# CW340_FPGA_CFG.net
KiCad netlist of a schematic drawn in Altium Designer
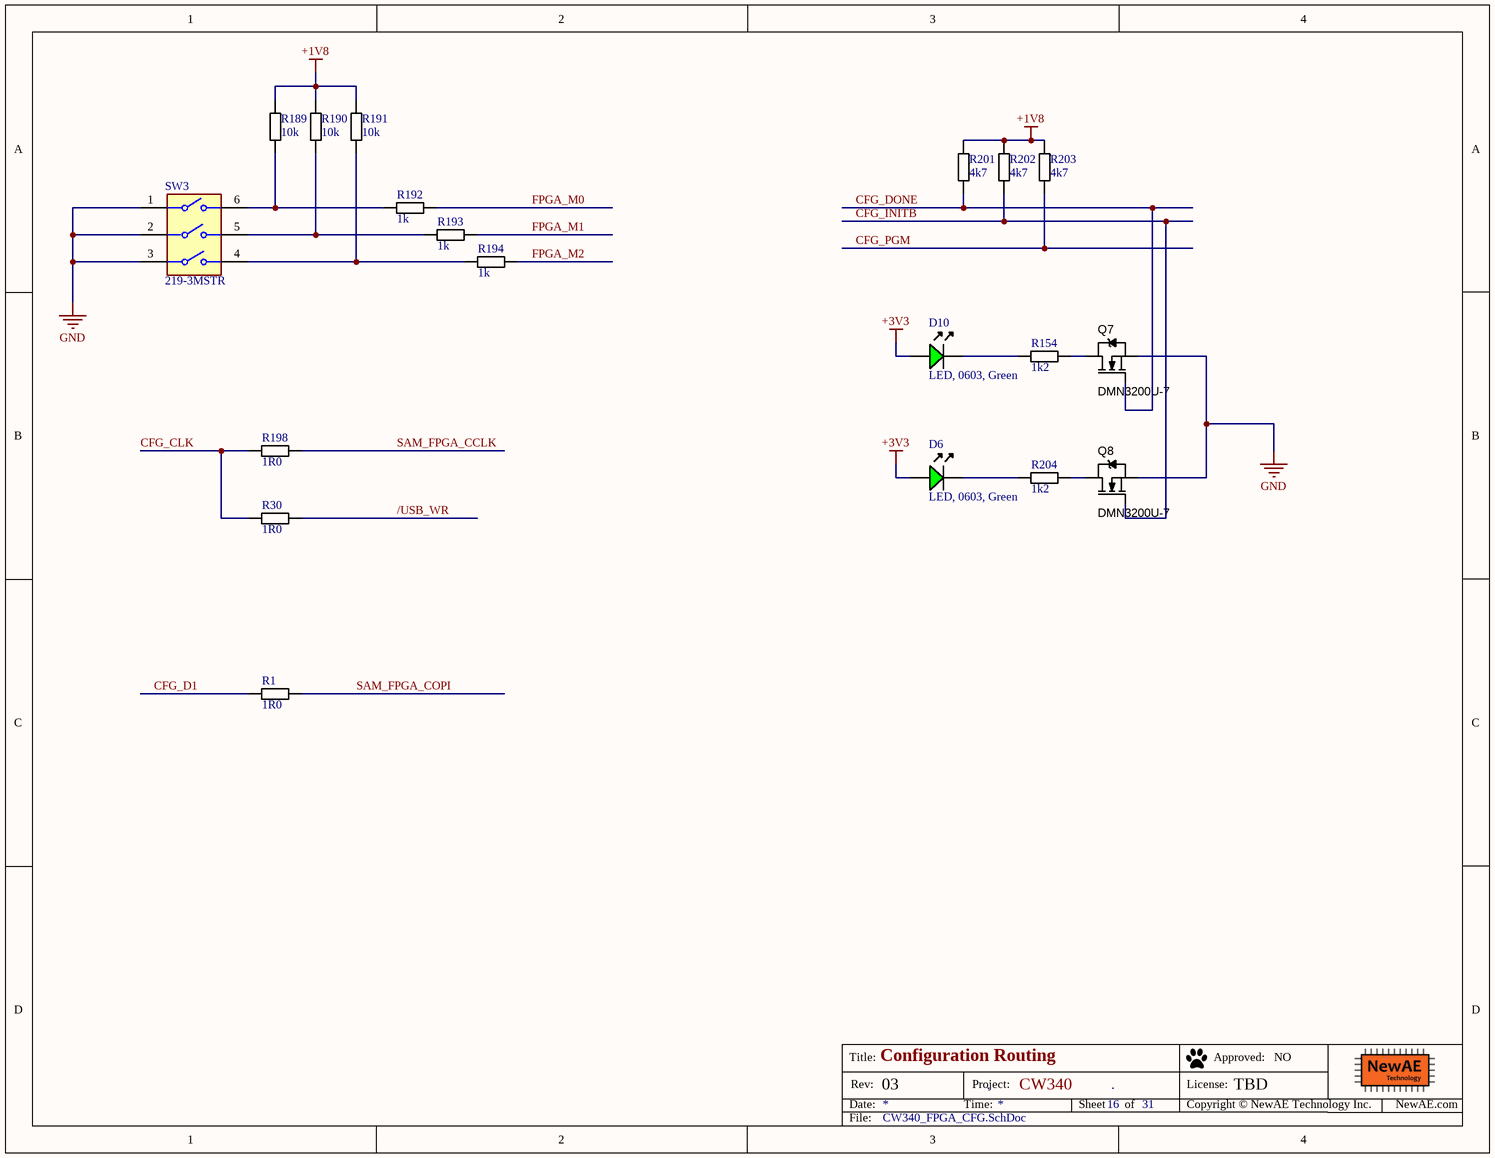
[diagram p0: CW340_FPGA_CFG.SchDoc]

(export (version "E")
  (design (tool "Eeschema 10.0.6"))
  (components
    (comp (ref "D6")
      (value "LED, 0603, Green")
      (footprint "LED-0603-GREEN")
      (description "Chip LED, Green")
      (fields (field (name "PART NUMBER") "LEDCHIP_0603_GREEN"))
      (libsource (lib "NewAE_AltiumLib") (part "LED_GREEN"))
    )
    (comp (ref "D10")
      (value "LED, 0603, Green")
      (footprint "LED-0603-GREEN")
      (description "Chip LED, Green")
      (fields (field (name "PART NUMBER") "LEDCHIP_0603_GREEN"))
      (libsource (lib "NewAE_AltiumLib") (part "LED_GREEN"))
    )
    (comp (ref "Q7")
      (value "DMN3200U-7")
      (footprint "SOT95P245X110-3M")
      (description "MOSFET N-CH 30V 2.2A SOT23-3")
      (libsource (lib "NewAE_AltiumLib") (part "MOSFET_N_GSD"))
    )
    (comp (ref "Q8")
      (value "DMN3200U-7")
      (footprint "SOT95P245X110-3M")
      (description "MOSFET N-CH 30V 2.2A SOT23-3")
      (libsource (lib "NewAE_AltiumLib") (part "MOSFET_N_GSD"))
    )
    (comp (ref "R1")
      (value "1R0")
      (footprint "RESC1608X55N")
      (description "1R0 res, 0603, 1%, 1/10W")
      (fields (field (name "PART NUMBER") "RCHIP-1R0-0603") (field (name "TOLERANCE") "1%"))
      (libsource (lib "") (part "RES-EU_1"))
    )
    (comp (ref "R30")
      (value "1R0")
      (footprint "RESC1608X55N")
      (description "1R0 res, 0603, 1%, 1/10W")
      (fields (field (name "PART NUMBER") "RCHIP-1R0-0603") (field (name "TOLERANCE") "1%"))
      (libsource (lib "") (part "RES-EU_1"))
    )
    (comp (ref "R154")
      (value "1k2")
      (footprint "RESC1005X40N")
      (description "1k2 res, 0402, 1%, 1/16W")
      (fields (field (name "PART NUMBER") "RCHIP-1K2-0402") (field (name "TOLERANCE") "1%"))
      (libsource (lib "") (part "RES-EU_1"))
    )
    (comp (ref "R189")
      (value "10k")
      (footprint "RESC1005X40N")
      (description "10k res, 0402, 1%, 1/16W")
      (fields (field (name "PART NUMBER") "RCHIP-10K-0402") (field (name "TOLERANCE") "1%"))
      (libsource (lib "NewAE_AltiumLib") (part "RES-EU"))
    )
    (comp (ref "R190")
      (value "10k")
      (footprint "RESC1005X40N")
      (description "10k res, 0402, 1%, 1/16W")
      (fields (field (name "PART NUMBER") "RCHIP-10K-0402") (field (name "TOLERANCE") "1%"))
      (libsource (lib "NewAE_AltiumLib") (part "RES-EU"))
    )
    (comp (ref "R191")
      (value "10k")
      (footprint "RESC1005X40N")
      (description "10k res, 0402, 1%, 1/16W")
      (fields (field (name "PART NUMBER") "RCHIP-10K-0402") (field (name "TOLERANCE") "1%"))
      (libsource (lib "NewAE_AltiumLib") (part "RES-EU"))
    )
    (comp (ref "R192")
      (value "1k")
      (footprint "RESC1005X40N")
      (description "1k res, 0402, 1%, 1/16W")
      (fields (field (name "PART NUMBER") "RCHIP-1K-0402") (field (name "TOLERANCE") "1%"))
      (libsource (lib "") (part "RES-EU_1"))
    )
    (comp (ref "R193")
      (value "1k")
      (footprint "RESC1005X40N")
      (description "1k res, 0402, 1%, 1/16W")
      (fields (field (name "PART NUMBER") "RCHIP-1K-0402") (field (name "TOLERANCE") "1%"))
      (libsource (lib "") (part "RES-EU_1"))
    )
    (comp (ref "R194")
      (value "1k")
      (footprint "RESC1005X40N")
      (description "1k res, 0402, 1%, 1/16W")
      (fields (field (name "PART NUMBER") "RCHIP-1K-0402") (field (name "TOLERANCE") "1%"))
      (libsource (lib "") (part "RES-EU_1"))
    )
    (comp (ref "R198")
      (value "1R0")
      (footprint "RESC1608X55N")
      (description "1R0 res, 0603, 1%, 1/10W")
      (fields (field (name "PART NUMBER") "RCHIP-1R0-0603") (field (name "TOLERANCE") "1%"))
      (libsource (lib "") (part "RES-EU_1"))
    )
    (comp (ref "R201")
      (value "4k7")
      (footprint "RESC1005X40N")
      (description "4k7 res, 0402, 1%, 1/16W")
      (fields (field (name "PART NUMBER") "RCHIP-4K7-0402") (field (name "TOLERANCE") "1%"))
      (libsource (lib "NewAE_AltiumLib") (part "RES-EU"))
    )
    (comp (ref "R202")
      (value "4k7")
      (footprint "RESC1005X40N")
      (description "4k7 res, 0402, 1%, 1/16W")
      (fields (field (name "PART NUMBER") "RCHIP-4K7-0402") (field (name "TOLERANCE") "1%"))
      (libsource (lib "NewAE_AltiumLib") (part "RES-EU"))
    )
    (comp (ref "R203")
      (value "4k7")
      (footprint "RESC1005X40N")
      (description "4k7 res, 0402, 1%, 1/16W")
      (fields (field (name "PART NUMBER") "RCHIP-4K7-0402") (field (name "TOLERANCE") "1%"))
      (libsource (lib "NewAE_AltiumLib") (part "RES-EU"))
    )
    (comp (ref "R204")
      (value "1k2")
      (footprint "RESC1005X40N")
      (description "1k2 res, 0402, 1%, 1/16W")
      (fields (field (name "PART NUMBER") "RCHIP-1K2-0402") (field (name "TOLERANCE") "1%"))
      (libsource (lib "") (part "RES-EU_1"))
    )
    (comp (ref "SW3")
      (value "219-3MSTR")
      (footprint "FP-219-3MSTR-MFG")
      (description "SWITCH SLIDE DIP SPST 100MA 20V")
      (libsource (lib "Altium Content Vault") (part "7c490946f25aa2bb1cd4cef5bc3ec4e"))
    )
  )
  (nets
    (net (code "1") (name "+1V8") (class "Default")
      (node (ref "R189") (pin "1") (pinfunction "1_1") (pintype "passive"))
      (node (ref "R190") (pin "1") (pinfunction "1_1") (pintype "passive"))
      (node (ref "R191") (pin "1") (pinfunction "1_1") (pintype "passive"))
      (node (ref "R201") (pin "1") (pinfunction "1_1") (pintype "passive"))
      (node (ref "R202") (pin "1") (pinfunction "1_1") (pintype "passive"))
      (node (ref "R203") (pin "1") (pinfunction "1_1") (pintype "passive"))
    )
    (net (code "2") (name "+3V3") (class "Default")
      (node (ref "D10") (pin "A") (pinfunction "A_A") (pintype "passive"))
      (node (ref "D6") (pin "A") (pinfunction "A_A") (pintype "passive"))
    )
    (net (code "3") (name "/CFG_CLK") (class "Default")
      (node (ref "R198") (pin "1") (pinfunction "1_1") (pintype "passive"))
      (node (ref "R30") (pin "1") (pinfunction "1_1") (pintype "passive"))
    )
    (net (code "4") (name "/CFG_D1") (class "Default")
      (node (ref "R1") (pin "1") (pinfunction "1_1") (pintype "passive"))
    )
    (net (code "5") (name "/CFG_DONE") (class "Default")
      (node (ref "Q7") (pin "1") (pinfunction "G_1") (pintype "passive"))
      (node (ref "R201") (pin "2") (pinfunction "2_2") (pintype "passive"))
    )
    (net (code "6") (name "/CFG_INITB") (class "Default")
      (node (ref "Q8") (pin "1") (pinfunction "G_1") (pintype "passive"))
      (node (ref "R202") (pin "2") (pinfunction "2_2") (pintype "passive"))
    )
    (net (code "7") (name "/CFG_PGM") (class "Default")
      (node (ref "R203") (pin "2") (pinfunction "2_2") (pintype "passive"))
    )
    (net (code "8") (name "/FPGA_M0") (class "Default")
      (node (ref "R192") (pin "2") (pinfunction "2_2") (pintype "passive"))
    )
    (net (code "9") (name "/FPGA_M1") (class "Default")
      (node (ref "R193") (pin "2") (pinfunction "2_2") (pintype "passive"))
    )
    (net (code "10") (name "/FPGA_M2") (class "Default")
      (node (ref "R194") (pin "2") (pinfunction "2_2") (pintype "passive"))
    )
    (net (code "11") (name "/SAM_FPGA_CCLK") (class "Default")
      (node (ref "R198") (pin "2") (pinfunction "2_2") (pintype "passive"))
    )
    (net (code "12") (name "/SAM_FPGA_COPI") (class "Default")
      (node (ref "R1") (pin "2") (pinfunction "2_2") (pintype "passive"))
    )
    (net (code "13") (name "/{slash}USB_WR") (class "Default")
      (node (ref "R30") (pin "2") (pinfunction "2_2") (pintype "passive"))
    )
    (net (code "14") (name "GND") (class "Default")
      (node (ref "Q7") (pin "2") (pinfunction "S_2") (pintype "passive"))
      (node (ref "Q8") (pin "2") (pinfunction "S_2") (pintype "passive"))
      (node (ref "SW3") (pin "1") (pinfunction "1_1") (pintype "passive"))
      (node (ref "SW3") (pin "2") (pinfunction "2_2") (pintype "passive"))
      (node (ref "SW3") (pin "3") (pinfunction "3_3") (pintype "passive"))
    )
    (net (code "15") (name "Net-(D6-PadK)") (class "Default")
      (node (ref "D6") (pin "K") (pinfunction "K_K") (pintype "passive"))
      (node (ref "R204") (pin "1") (pinfunction "1_1") (pintype "passive"))
    )
    (net (code "16") (name "Net-(D10-PadK)") (class "Default")
      (node (ref "D10") (pin "K") (pinfunction "K_K") (pintype "passive"))
      (node (ref "R154") (pin "1") (pinfunction "1_1") (pintype "passive"))
    )
    (net (code "17") (name "Net-(Q7-D)") (class "Default")
      (node (ref "Q7") (pin "3") (pinfunction "D_3") (pintype "passive"))
      (node (ref "R154") (pin "2") (pinfunction "2_2") (pintype "passive"))
    )
    (net (code "18") (name "Net-(Q8-D)") (class "Default")
      (node (ref "Q8") (pin "3") (pinfunction "D_3") (pintype "passive"))
      (node (ref "R204") (pin "2") (pinfunction "2_2") (pintype "passive"))
    )
    (net (code "19") (name "Net-(R189-Pad2)") (class "Default")
      (node (ref "R189") (pin "2") (pinfunction "2_2") (pintype "passive"))
      (node (ref "R192") (pin "1") (pinfunction "1_1") (pintype "passive"))
      (node (ref "SW3") (pin "6") (pinfunction "6_6") (pintype "passive"))
    )
    (net (code "20") (name "Net-(R190-Pad2)") (class "Default")
      (node (ref "R190") (pin "2") (pinfunction "2_2") (pintype "passive"))
      (node (ref "R193") (pin "1") (pinfunction "1_1") (pintype "passive"))
      (node (ref "SW3") (pin "5") (pinfunction "5_5") (pintype "passive"))
    )
    (net (code "21") (name "Net-(R191-Pad2)") (class "Default")
      (node (ref "R191") (pin "2") (pinfunction "2_2") (pintype "passive"))
      (node (ref "R194") (pin "1") (pinfunction "1_1") (pintype "passive"))
      (node (ref "SW3") (pin "4") (pinfunction "4_4") (pintype "passive"))
    )
  )
)
